# XBee-Adapter_v11.net
KiCad netlist of a schematic drawn in EAGLE
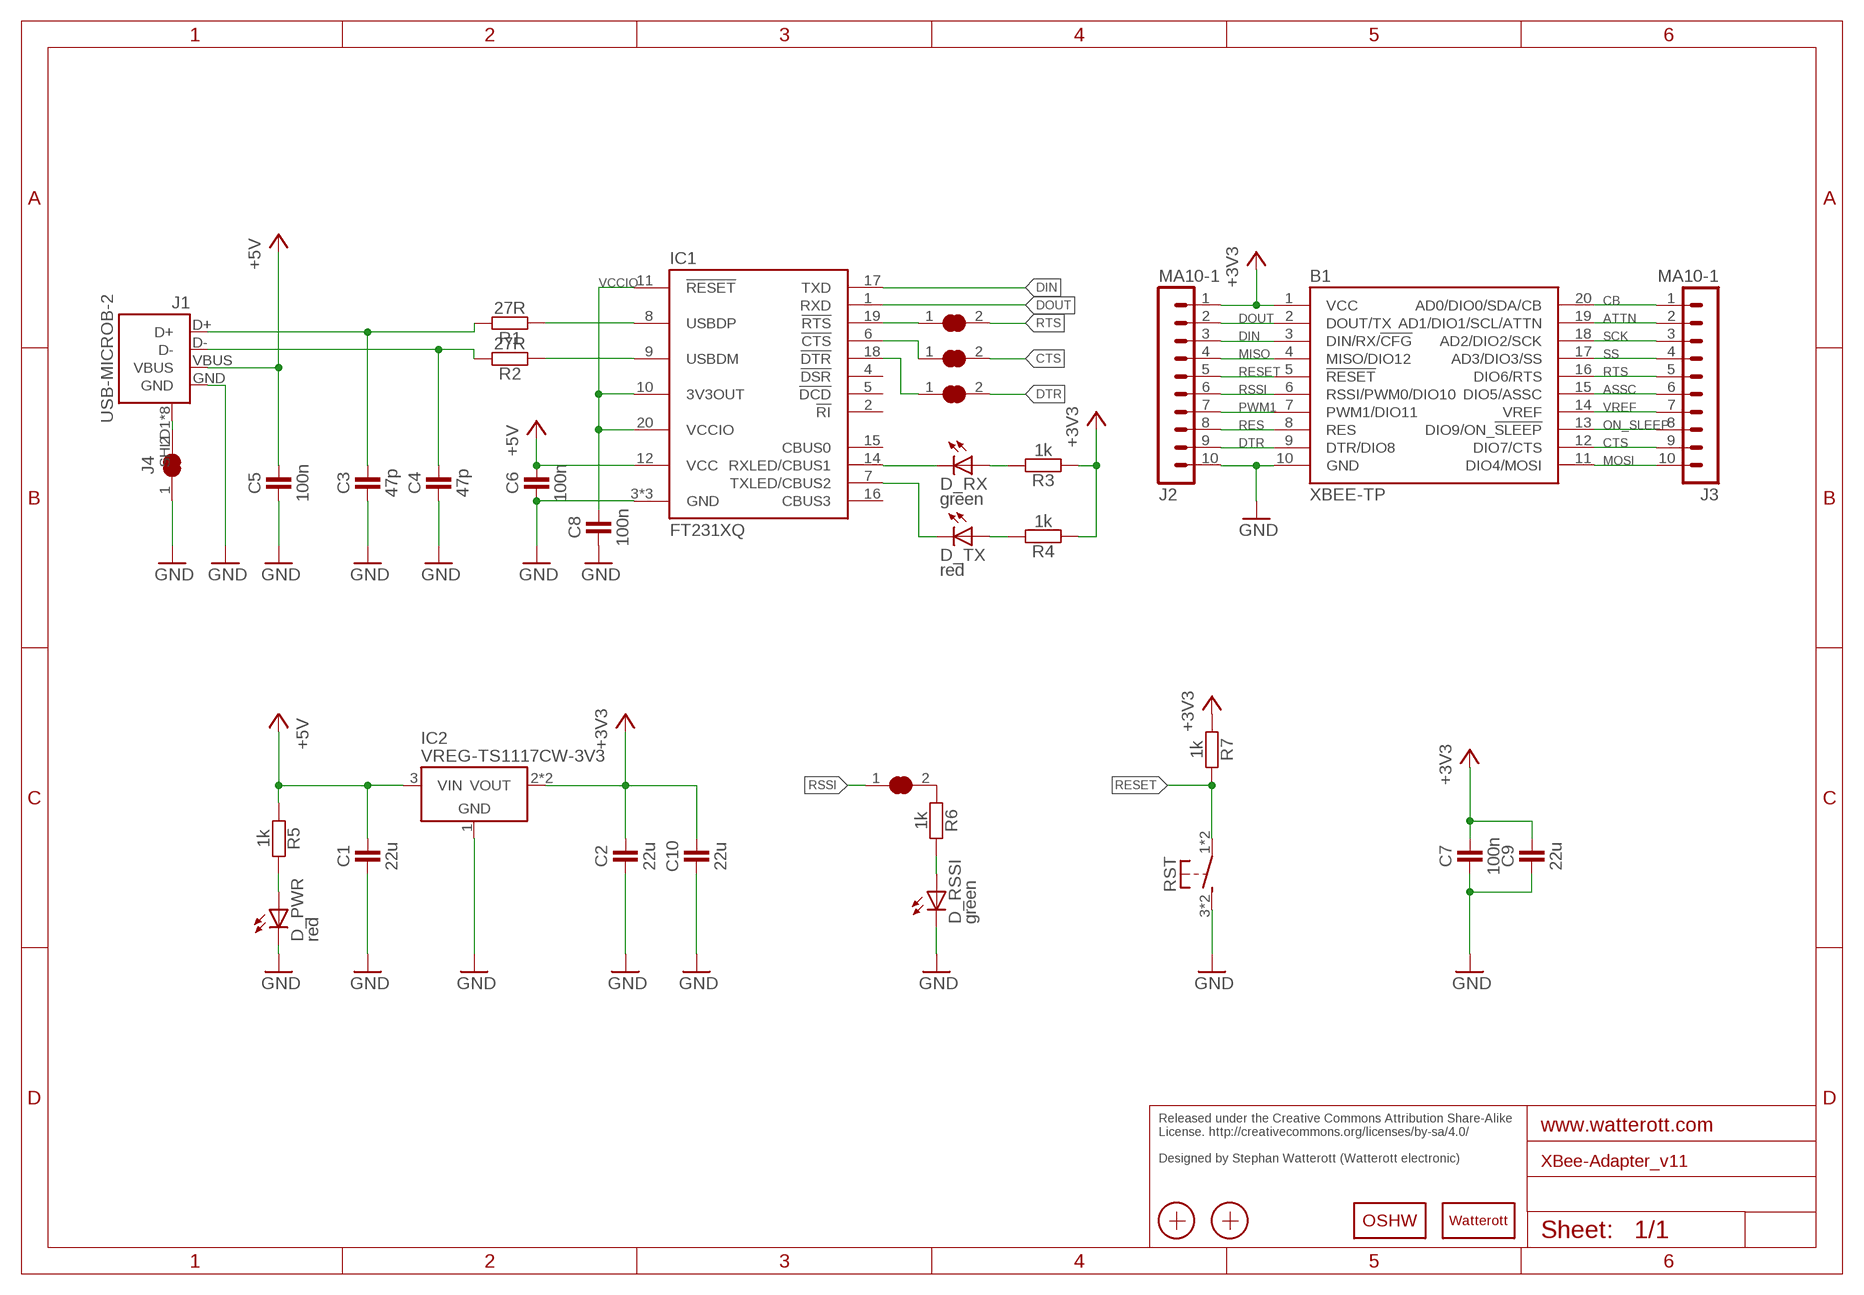
[diagram p0: schematic, sheet 1]

(export (version "E")
  (design (tool "Eeschema 10.0.6"))
  (components
    (comp (ref "B1")
      (value "XBEE-TP")
      (footprint "eagle-import:XBEE_TP")
      (libsource (lib "eagle-import") (part "XBEE-TP"))
    )
    (comp (ref "C1")
      (value "22u")
      (footprint "eagle-import:C0805")
      (libsource (lib "eagle-import") (part "CAPACITOR-0805"))
    )
    (comp (ref "C2")
      (value "22u")
      (footprint "eagle-import:C0805")
      (libsource (lib "eagle-import") (part "CAPACITOR-0805"))
    )
    (comp (ref "C3")
      (value "47p")
      (footprint "eagle-import:C0402")
      (libsource (lib "eagle-import") (part "CAPACITOR-0402"))
    )
    (comp (ref "C4")
      (value "47p")
      (footprint "eagle-import:C0402")
      (libsource (lib "eagle-import") (part "CAPACITOR-0402"))
    )
    (comp (ref "C5")
      (value "100n")
      (footprint "eagle-import:C0402")
      (libsource (lib "eagle-import") (part "CAPACITOR-0402"))
    )
    (comp (ref "C6")
      (value "100n")
      (footprint "eagle-import:C0402")
      (libsource (lib "eagle-import") (part "CAPACITOR-0402"))
    )
    (comp (ref "C7")
      (value "100n")
      (footprint "eagle-import:C0402")
      (libsource (lib "eagle-import") (part "CAPACITOR-0402"))
    )
    (comp (ref "C8")
      (value "100n")
      (footprint "eagle-import:C0402")
      (libsource (lib "eagle-import") (part "CAPACITOR-0402"))
    )
    (comp (ref "C9")
      (value "22u")
      (footprint "eagle-import:C0805")
      (libsource (lib "eagle-import") (part "CAPACITOR-0805"))
    )
    (comp (ref "C10")
      (value "22u")
      (footprint "eagle-import:C0805")
      (libsource (lib "eagle-import") (part "CAPACITOR-0805"))
    )
    (comp (ref "CTS")
      (value "JUMPER2-0603")
      (footprint "eagle-import:JUMPER2-0603")
      (libsource (lib "eagle-import") (part "JUMPER2-0603"))
    )
    (comp (ref "DTR")
      (value "JUMPER2-0603")
      (footprint "eagle-import:JUMPER2-0603")
      (libsource (lib "eagle-import") (part "JUMPER2-0603"))
    )
    (comp (ref "D_PWR")
      (value "red")
      (footprint "eagle-import:C0603")
      (libsource (lib "eagle-import") (part "LED-0603"))
    )
    (comp (ref "D_RSSI")
      (value "green")
      (footprint "eagle-import:C0603")
      (libsource (lib "eagle-import") (part "LED-0603"))
    )
    (comp (ref "D_RX")
      (value "green")
      (footprint "eagle-import:C0603")
      (libsource (lib "eagle-import") (part "LED-0603"))
    )
    (comp (ref "D_TX")
      (value "red")
      (footprint "eagle-import:C0603")
      (libsource (lib "eagle-import") (part "LED-0603"))
    )
    (comp (ref "IC1")
      (value "FT231XQ")
      (footprint "eagle-import:QFN20-PAD")
      (libsource (lib "eagle-import") (part "FT231XQ"))
    )
    (comp (ref "IC2")
      (value "VREG-TS1117CW-3V3")
      (footprint "eagle-import:SOT223")
      (libsource (lib "eagle-import") (part "VREG-TS1117CW-3V3"))
    )
    (comp (ref "J1")
      (value "USB-MICROB-2")
      (footprint "eagle-import:USB-MICROB-10118194")
      (libsource (lib "eagle-import") (part "USB-MICROB-2"))
    )
    (comp (ref "J2")
      (value "MA10-1")
      (footprint "eagle-import:MA10-1")
      (libsource (lib "eagle-import") (part "MA10-1"))
    )
    (comp (ref "J3")
      (value "MA10-1")
      (footprint "eagle-import:MA10-1")
      (libsource (lib "eagle-import") (part "MA10-1"))
    )
    (comp (ref "J4")
      (value "JUMPER2-0603")
      (footprint "eagle-import:JUMPER2-0603")
      (libsource (lib "eagle-import") (part "JUMPER2-0603"))
    )
    (comp (ref "LOGO1")
      (value "OSHW_LOGOX0150")
      (footprint "eagle-import:OSHW_6X150")
      (libsource (lib "eagle-import") (part "OSHW_LOGOX0150"))
    )
    (comp (ref "LOGO2")
      (value "LOGO-S_PLACE_M")
      (footprint "eagle-import:SPARK_TPLACE_M")
      (libsource (lib "eagle-import") (part "LOGO-S_PLACE_M"))
    )
    (comp (ref "R1")
      (value "27R")
      (footprint "eagle-import:C0603")
      (libsource (lib "eagle-import") (part "RESISTOR-0603"))
    )
    (comp (ref "R2")
      (value "27R")
      (footprint "eagle-import:C0603")
      (libsource (lib "eagle-import") (part "RESISTOR-0603"))
    )
    (comp (ref "R3")
      (value "1k")
      (footprint "eagle-import:C0402")
      (libsource (lib "eagle-import") (part "RESISTOR-0402"))
    )
    (comp (ref "R4")
      (value "1k")
      (footprint "eagle-import:C0402")
      (libsource (lib "eagle-import") (part "RESISTOR-0402"))
    )
    (comp (ref "R5")
      (value "1k")
      (footprint "eagle-import:C0402")
      (libsource (lib "eagle-import") (part "RESISTOR-0402"))
    )
    (comp (ref "R6")
      (value "1k")
      (footprint "eagle-import:C0402")
      (libsource (lib "eagle-import") (part "RESISTOR-0402"))
    )
    (comp (ref "R7")
      (value "1k")
      (footprint "eagle-import:C0402")
      (libsource (lib "eagle-import") (part "RESISTOR-0402"))
    )
    (comp (ref "RSSI")
      (value "JUMPER2-0603")
      (footprint "eagle-import:JUMPER2-0603")
      (libsource (lib "eagle-import") (part "JUMPER2-0603"))
    )
    (comp (ref "RST")
      (value "SW-TACTILE-PTS840P")
      (footprint "eagle-import:PTS840P")
      (libsource (lib "eagle-import") (part "SW-TACTILE-PTS840P"))
    )
    (comp (ref "RTS")
      (value "JUMPER2-0603")
      (footprint "eagle-import:JUMPER2-0603")
      (libsource (lib "eagle-import") (part "JUMPER2-0603"))
    )
    (comp (ref "X1")
      (value "PASSER-07")
      (footprint "eagle-import:PASSER_07MM")
      (libsource (lib "eagle-import") (part "PASSER-07"))
    )
    (comp (ref "X2")
      (value "PASSER-07")
      (footprint "eagle-import:PASSER_07MM")
      (libsource (lib "eagle-import") (part "PASSER-07"))
    )
  )
  (nets
    (net (code "1") (name "+3V3") (class "Default")
      (node (ref "B1") (pin "1") (pinfunction "VCC_1") (pintype "power_in"))
      (node (ref "C10") (pin "2") (pinfunction "2_2") (pintype "passive"))
      (node (ref "C2") (pin "2") (pinfunction "2_2") (pintype "passive"))
      (node (ref "C7") (pin "2") (pinfunction "2_2") (pintype "passive"))
      (node (ref "C9") (pin "2") (pinfunction "2_2") (pintype "passive"))
      (node (ref "IC2") (pin "2") (pinfunction "VOUT_2") (pintype "power_in"))
      (node (ref "IC2") (pin "4") (pinfunction "VOUT_4") (pintype "power_in"))
      (node (ref "J2") (pin "1") (pinfunction "1_1") (pintype "passive"))
      (node (ref "R3") (pin "1") (pinfunction "1_1") (pintype "passive"))
      (node (ref "R4") (pin "1") (pinfunction "1_1") (pintype "passive"))
      (node (ref "R7") (pin "1") (pinfunction "1_1") (pintype "passive"))
    )
    (net (code "2") (name "+5V") (class "Default")
      (node (ref "C1") (pin "2") (pinfunction "2_2") (pintype "passive"))
      (node (ref "C5") (pin "2") (pinfunction "2_2") (pintype "passive"))
      (node (ref "C6") (pin "2") (pinfunction "2_2") (pintype "passive"))
      (node (ref "IC1") (pin "12") (pinfunction "VCC_12") (pintype "power_in"))
      (node (ref "IC2") (pin "3") (pinfunction "VIN_3") (pintype "power_in"))
      (node (ref "J1") (pin "VBUS") (pinfunction "VBUS_VBUS") (pintype "power_in"))
      (node (ref "R5") (pin "1") (pinfunction "1_1") (pintype "passive"))
    )
    (net (code "3") (name "/ASSC") (class "Default")
      (node (ref "B1") (pin "15") (pinfunction "DIO5/ASSC_15") (pintype "bidirectional"))
      (node (ref "J3") (pin "6") (pinfunction "6_6") (pintype "passive"))
    )
    (net (code "4") (name "/ATTN") (class "Default")
      (node (ref "B1") (pin "19") (pinfunction "AD1/DIO1/SCL/ATTN_19") (pintype "bidirectional"))
      (node (ref "J3") (pin "2") (pinfunction "2_2") (pintype "passive"))
    )
    (net (code "5") (name "/CB") (class "Default")
      (node (ref "B1") (pin "20") (pinfunction "AD0/DIO0/SDA/CB_20") (pintype "bidirectional"))
      (node (ref "J3") (pin "1") (pinfunction "1_1") (pintype "passive"))
    )
    (net (code "6") (name "/MISO") (class "Default")
      (node (ref "B1") (pin "4") (pinfunction "MISO/DIO12_4") (pintype "bidirectional"))
      (node (ref "J2") (pin "4") (pinfunction "4_4") (pintype "passive"))
    )
    (net (code "7") (name "/MOSI") (class "Default")
      (node (ref "B1") (pin "11") (pinfunction "DIO4/MOSI_11") (pintype "bidirectional"))
      (node (ref "J3") (pin "10") (pinfunction "10_10") (pintype "passive"))
    )
    (net (code "8") (name "/ON_SLEEP") (class "Default")
      (node (ref "B1") (pin "13") (pinfunction "DIO9/ON_~{SLEEP}_13") (pintype "bidirectional"))
      (node (ref "J3") (pin "8") (pinfunction "8_8") (pintype "passive"))
    )
    (net (code "9") (name "/PWM1") (class "Default")
      (node (ref "B1") (pin "7") (pinfunction "PWM1/DIO11_7") (pintype "bidirectional"))
      (node (ref "J2") (pin "7") (pinfunction "7_7") (pintype "passive"))
    )
    (net (code "10") (name "/RES") (class "Default")
      (node (ref "B1") (pin "8") (pinfunction "RES_8") (pintype "bidirectional"))
      (node (ref "J2") (pin "8") (pinfunction "8_8") (pintype "passive"))
    )
    (net (code "11") (name "/SCK") (class "Default")
      (node (ref "B1") (pin "18") (pinfunction "AD2/DIO2/SCK_18") (pintype "bidirectional"))
      (node (ref "J3") (pin "3") (pinfunction "3_3") (pintype "passive"))
    )
    (net (code "12") (name "/SS") (class "Default")
      (node (ref "B1") (pin "17") (pinfunction "AD3/DIO3/SS_17") (pintype "bidirectional"))
      (node (ref "J3") (pin "4") (pinfunction "4_4") (pintype "passive"))
    )
    (net (code "13") (name "/VCCIO") (class "Default")
      (node (ref "C8") (pin "2") (pinfunction "2_2") (pintype "passive"))
      (node (ref "IC1") (pin "10") (pinfunction "3V3OUT_10") (pintype "power_in"))
      (node (ref "IC1") (pin "11") (pinfunction "~{RESET}_11") (pintype "bidirectional"))
      (node (ref "IC1") (pin "20") (pinfunction "VCCIO_20") (pintype "power_in"))
    )
    (net (code "14") (name "/VREF") (class "Default")
      (node (ref "B1") (pin "14") (pinfunction "VREF_14") (pintype "bidirectional"))
      (node (ref "J3") (pin "7") (pinfunction "7_7") (pintype "passive"))
    )
    (net (code "15") (name "CTS") (class "Default")
      (node (ref "B1") (pin "12") (pinfunction "DIO7/CTS_12") (pintype "bidirectional"))
      (node (ref "CTS") (pin "2") (pinfunction "2_2") (pintype "passive"))
      (node (ref "J3") (pin "9") (pinfunction "9_9") (pintype "passive"))
    )
    (net (code "16") (name "DIN") (class "Default")
      (node (ref "B1") (pin "3") (pinfunction "DIN/RX/~{CFG}_3") (pintype "bidirectional"))
      (node (ref "IC1") (pin "17") (pinfunction "TXD_17") (pintype "bidirectional"))
      (node (ref "J2") (pin "3") (pinfunction "3_3") (pintype "passive"))
    )
    (net (code "17") (name "DOUT") (class "Default")
      (node (ref "B1") (pin "2") (pinfunction "DOUT/TX_2") (pintype "bidirectional"))
      (node (ref "IC1") (pin "1") (pinfunction "RXD_1") (pintype "bidirectional"))
      (node (ref "J2") (pin "2") (pinfunction "2_2") (pintype "passive"))
    )
    (net (code "18") (name "DTR") (class "Default")
      (node (ref "B1") (pin "9") (pinfunction "DTR/DIO8_9") (pintype "bidirectional"))
      (node (ref "DTR") (pin "2") (pinfunction "2_2") (pintype "passive"))
      (node (ref "J2") (pin "9") (pinfunction "9_9") (pintype "passive"))
    )
    (net (code "19") (name "GND") (class "Default")
      (node (ref "B1") (pin "10") (pinfunction "GND_10") (pintype "power_in"))
      (node (ref "C1") (pin "1") (pinfunction "1_1") (pintype "passive"))
      (node (ref "C10") (pin "1") (pinfunction "1_1") (pintype "passive"))
      (node (ref "C2") (pin "1") (pinfunction "1_1") (pintype "passive"))
      (node (ref "C3") (pin "1") (pinfunction "1_1") (pintype "passive"))
      (node (ref "C4") (pin "1") (pinfunction "1_1") (pintype "passive"))
      (node (ref "C5") (pin "1") (pinfunction "1_1") (pintype "passive"))
      (node (ref "C6") (pin "1") (pinfunction "1_1") (pintype "passive"))
      (node (ref "C7") (pin "1") (pinfunction "1_1") (pintype "passive"))
      (node (ref "C8") (pin "1") (pinfunction "1_1") (pintype "passive"))
      (node (ref "C9") (pin "1") (pinfunction "1_1") (pintype "passive"))
      (node (ref "D_PWR") (pin "C") (pinfunction "C_C") (pintype "passive"))
      (node (ref "D_RSSI") (pin "C") (pinfunction "C_C") (pintype "passive"))
      (node (ref "IC1") (pin "13") (pinfunction "GND_13") (pintype "power_in"))
      (node (ref "IC1") (pin "3") (pinfunction "GND_3") (pintype "power_in"))
      (node (ref "IC1") (pin "TP") (pinfunction "GND_TP") (pintype "power_in"))
      (node (ref "IC2") (pin "1") (pinfunction "GND_1") (pintype "power_in"))
      (node (ref "J1") (pin "GND") (pinfunction "GND_GND") (pintype "power_in"))
      (node (ref "J2") (pin "10") (pinfunction "10_10") (pintype "passive"))
      (node (ref "J4") (pin "1") (pinfunction "1_1") (pintype "passive"))
      (node (ref "RST") (pin "3") (pinfunction "S1_3") (pintype "passive"))
      (node (ref "RST") (pin "4") (pinfunction "S1_4") (pintype "passive"))
    )
    (net (code "20") (name "Net-(C3-Pad2)") (class "Default")
      (node (ref "C3") (pin "2") (pinfunction "2_2") (pintype "passive"))
      (node (ref "J1") (pin "D+") (pinfunction "D+_D+") (pintype "bidirectional"))
      (node (ref "R1") (pin "2") (pinfunction "2_2") (pintype "passive"))
    )
    (net (code "21") (name "Net-(C4-Pad2)") (class "Default")
      (node (ref "C4") (pin "2") (pinfunction "2_2") (pintype "passive"))
      (node (ref "J1") (pin "D-") (pinfunction "D-_D-") (pintype "bidirectional"))
      (node (ref "R2") (pin "2") (pinfunction "2_2") (pintype "passive"))
    )
    (net (code "22") (name "Net-(D_PWR-PadA)") (class "Default")
      (node (ref "D_PWR") (pin "A") (pinfunction "A_A") (pintype "passive"))
      (node (ref "R5") (pin "2") (pinfunction "2_2") (pintype "passive"))
    )
    (net (code "23") (name "Net-(D_RSSI-PadA)") (class "Default")
      (node (ref "D_RSSI") (pin "A") (pinfunction "A_A") (pintype "passive"))
      (node (ref "R6") (pin "2") (pinfunction "2_2") (pintype "passive"))
    )
    (net (code "24") (name "Net-(D_RX-PadA)") (class "Default")
      (node (ref "D_RX") (pin "A") (pinfunction "A_A") (pintype "passive"))
      (node (ref "R3") (pin "2") (pinfunction "2_2") (pintype "passive"))
    )
    (net (code "25") (name "Net-(D_TX-PadA)") (class "Default")
      (node (ref "D_TX") (pin "A") (pinfunction "A_A") (pintype "passive"))
      (node (ref "R4") (pin "2") (pinfunction "2_2") (pintype "passive"))
    )
    (net (code "26") (name "Net-(IC1-RXLED{slash}CBUS1)") (class "Default")
      (node (ref "D_RX") (pin "C") (pinfunction "C_C") (pintype "passive"))
      (node (ref "IC1") (pin "14") (pinfunction "RXLED/CBUS1_14") (pintype "bidirectional"))
    )
    (net (code "27") (name "Net-(IC1-TXLED{slash}CBUS2)") (class "Default")
      (node (ref "D_TX") (pin "C") (pinfunction "C_C") (pintype "passive"))
      (node (ref "IC1") (pin "7") (pinfunction "TXLED/CBUS2_7") (pintype "bidirectional"))
    )
    (net (code "28") (name "Net-(IC1-USBDM)") (class "Default")
      (node (ref "IC1") (pin "9") (pinfunction "USBDM_9") (pintype "bidirectional"))
      (node (ref "R2") (pin "1") (pinfunction "1_1") (pintype "passive"))
    )
    (net (code "29") (name "Net-(IC1-USBDP)") (class "Default")
      (node (ref "IC1") (pin "8") (pinfunction "USBDP_8") (pintype "bidirectional"))
      (node (ref "R1") (pin "1") (pinfunction "1_1") (pintype "passive"))
    )
    (net (code "30") (name "Net-(IC1-~{CTS})") (class "Default")
      (node (ref "CTS") (pin "1") (pinfunction "1_1") (pintype "passive"))
      (node (ref "IC1") (pin "6") (pinfunction "~{CTS}_6") (pintype "bidirectional"))
    )
    (net (code "31") (name "Net-(IC1-~{DTR})") (class "Default")
      (node (ref "DTR") (pin "1") (pinfunction "1_1") (pintype "passive"))
      (node (ref "IC1") (pin "18") (pinfunction "~{DTR}_18") (pintype "bidirectional"))
    )
    (net (code "32") (name "Net-(IC1-~{RTS})") (class "Default")
      (node (ref "IC1") (pin "19") (pinfunction "~{RTS}_19") (pintype "bidirectional"))
      (node (ref "RTS") (pin "1") (pinfunction "1_1") (pintype "passive"))
    )
    (net (code "33") (name "Net-(J1-SHIELD-PadSHLD1)") (class "Default")
      (node (ref "J1") (pin "SHLD1") (pinfunction "SHIELD_SHLD1") (pintype "passive"))
      (node (ref "J1") (pin "SHLD2") (pinfunction "SHIELD_SHLD2") (pintype "passive"))
      (node (ref "J1") (pin "SHLD3") (pinfunction "SHIELD_SHLD3") (pintype "passive"))
      (node (ref "J1") (pin "SHLD4") (pinfunction "SHIELD_SHLD4") (pintype "passive"))
      (node (ref "J1") (pin "SHLD5") (pinfunction "SHIELD_SHLD5") (pintype "passive"))
      (node (ref "J1") (pin "SHLD6") (pinfunction "SHIELD_SHLD6") (pintype "passive"))
      (node (ref "J1") (pin "SHLD7") (pinfunction "SHIELD_SHLD7") (pintype "passive"))
      (node (ref "J1") (pin "SHLD8") (pinfunction "SHIELD_SHLD8") (pintype "passive"))
      (node (ref "J4") (pin "2") (pinfunction "2_2") (pintype "passive"))
    )
    (net (code "34") (name "Net-(R6-Pad1)") (class "Default")
      (node (ref "R6") (pin "1") (pinfunction "1_1") (pintype "passive"))
      (node (ref "RSSI") (pin "2") (pinfunction "2_2") (pintype "passive"))
    )
    (net (code "35") (name "RESET") (class "Default")
      (node (ref "B1") (pin "5") (pinfunction "~{RESET}_5") (pintype "bidirectional"))
      (node (ref "J2") (pin "5") (pinfunction "5_5") (pintype "passive"))
      (node (ref "R7") (pin "2") (pinfunction "2_2") (pintype "passive"))
      (node (ref "RST") (pin "1") (pinfunction "P1_1") (pintype "passive"))
      (node (ref "RST") (pin "2") (pinfunction "P1_2") (pintype "passive"))
    )
    (net (code "36") (name "RSSI") (class "Default")
      (node (ref "B1") (pin "6") (pinfunction "RSSI/PWM0/DIO10_6") (pintype "bidirectional"))
      (node (ref "J2") (pin "6") (pinfunction "6_6") (pintype "passive"))
      (node (ref "RSSI") (pin "1") (pinfunction "1_1") (pintype "passive"))
    )
    (net (code "37") (name "RTS") (class "Default")
      (node (ref "B1") (pin "16") (pinfunction "DIO6/RTS_16") (pintype "bidirectional"))
      (node (ref "J3") (pin "5") (pinfunction "5_5") (pintype "passive"))
      (node (ref "RTS") (pin "2") (pinfunction "2_2") (pintype "passive"))
    )
    (net (code "38") (name "unconnected-(IC1-CBUS0-Pad15)") (class "Default")
      (node (ref "IC1") (pin "15") (pinfunction "CBUS0_15") (pintype "bidirectional"))
    )
    (net (code "39") (name "unconnected-(IC1-CBUS3-Pad16)") (class "Default")
      (node (ref "IC1") (pin "16") (pinfunction "CBUS3_16") (pintype "bidirectional"))
    )
    (net (code "40") (name "unconnected-(IC1-~{DCD}-Pad5)") (class "Default")
      (node (ref "IC1") (pin "5") (pinfunction "~{DCD}_5") (pintype "bidirectional"))
    )
    (net (code "41") (name "unconnected-(IC1-~{DSR}-Pad4)") (class "Default")
      (node (ref "IC1") (pin "4") (pinfunction "~{DSR}_4") (pintype "bidirectional"))
    )
    (net (code "42") (name "unconnected-(IC1-~{RI}-Pad2)") (class "Default")
      (node (ref "IC1") (pin "2") (pinfunction "~{RI}_2") (pintype "bidirectional"))
    )
  )
)
